# Forward.net
KiCad netlist of a schematic drawn in Altium Designer
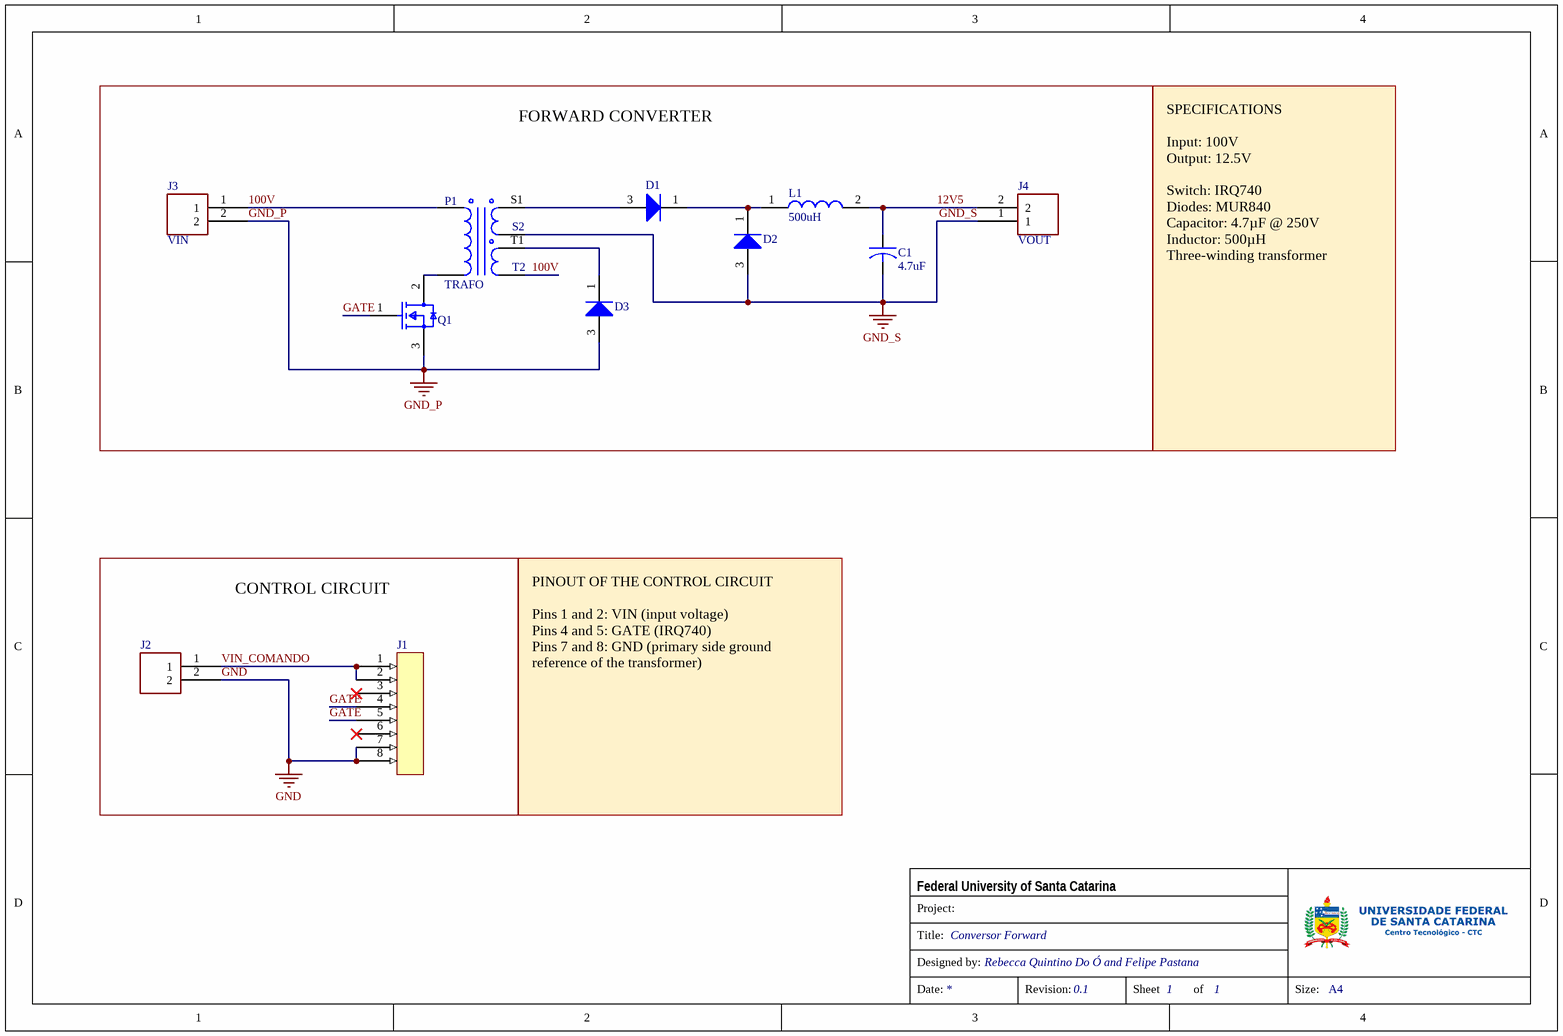
[diagram p0: Forward.SchDoc]

(export (version "E")
  (design (tool "Eeschema 10.0.6"))
  (components
    (comp (ref "C1")
      (value "4.7uF")
      (footprint "Capacitor")
      (description "Electrolytic capacitor")
      (libsource (lib "Elet_pot_2") (part "Capacitor Eletro"))
    )
    (comp (ref "D1")
      (value "MUR840G")
      (footprint "MUR840")
      (description "DIODE STANDARD 400V 8A TO2202")
      (libsource (lib "Elet_pot_2") (part "mur840"))
    )
    (comp (ref "D2")
      (value "MUR840G")
      (footprint "MUR840")
      (description "DIODE STANDARD 400V 8A TO2202")
      (libsource (lib "Elet_pot_2") (part "mur840"))
    )
    (comp (ref "D3")
      (value "MUR840G")
      (footprint "MUR840")
      (description "DIODE STANDARD 400V 8A TO2202")
      (libsource (lib "Elet_pot_2") (part "mur840"))
    )
    (comp (ref "J1")
      (value "header 8pin")
      (footprint "Header 8pin")
      (description "Header 8pin")
      (libsource (lib "Elet_pot_2") (part "header 8pin"))
    )
    (comp (ref "J2")
      (value "Con_Molex_2_pin")
      (footprint "CON_MOLEX_2_vias")
      (description "Connector KK Male 180° 2 Pins")
      (libsource (lib "Elet_pot_2") (part "Con_Molex_2_pin"))
    )
    (comp (ref "J3")
      (value "VIN")
      (footprint "Borne_KRE_2pin")
      (description "Connector Borne KRE 2 Vias")
      (libsource (lib "Elet_pot_2") (part "Borne_KRE_2_vias"))
    )
    (comp (ref "J4")
      (value "VOUT")
      (footprint "Borne_KRE_2pin")
      (description "Connector Borne KRE 2 Vias")
      (libsource (lib "") (part "Borne_KRE_2_vias_1"))
    )
    (comp (ref "L1")
      (value "500uH")
      (footprint "Indutor")
      (description "Indutor manufacture handmade")
      (libsource (lib "Elet_pot_2") (part "Indutor"))
    )
    (comp (ref "Q1")
      (value "IRF740")
      (footprint "IRF430")
      (description "MOSFET N-CH 400V 10A TO220AB")
      (libsource (lib "Elet_pot_2") (part "IRF740"))
    )
    (comp (ref "TRAFO")
      (value "Three-winding transformer")
      (footprint "Trafo_NEE_30/14")
      (description "Handmade three-winding transformer")
      (libsource (lib "Elet_pot_2") (part "Trafo"))
    )
  )
  (nets
    (net (code "1") (name "/12V5") (class "Default")
      (node (ref "C1") (pin "1") (pinfunction "1_1") (pintype "passive"))
      (node (ref "J4") (pin "2") (pinfunction "2_2") (pintype "passive"))
      (node (ref "L1") (pin "2") (pinfunction "2_2") (pintype "passive"))
    )
    (net (code "2") (name "/100V") (class "Default")
      (node (ref "J3") (pin "1") (pinfunction "1_1") (pintype "passive"))
      (node (ref "TRAFO") (pin "P1") (pinfunction "P1_P1") (pintype "passive"))
      (node (ref "TRAFO") (pin "S2") (pinfunction "S2_S2") (pintype "passive"))
    )
    (net (code "3") (name "/GATE") (class "Default")
      (node (ref "J1") (pin "4") (pinfunction "4_4") (pintype "input"))
      (node (ref "J1") (pin "5") (pinfunction "5_5") (pintype "input"))
      (node (ref "Q1") (pin "1") (pinfunction "G_1") (pintype "passive"))
    )
    (net (code "4") (name "/VIN_COMANDO") (class "Default")
      (node (ref "J1") (pin "1") (pinfunction "1_1") (pintype "input"))
      (node (ref "J1") (pin "2") (pinfunction "1_2") (pintype "input"))
      (node (ref "J2") (pin "1") (pinfunction "1_1") (pintype "passive"))
    )
    (net (code "5") (name "GND") (class "Default")
      (node (ref "J1") (pin "7") (pinfunction "7_7") (pintype "input"))
      (node (ref "J1") (pin "8") (pinfunction "8_8") (pintype "input"))
      (node (ref "J2") (pin "2") (pinfunction "2_2") (pintype "passive"))
    )
    (net (code "6") (name "GND_P") (class "Default")
      (node (ref "D3") (pin "3") (pinfunction "A_3") (pintype "passive"))
      (node (ref "J3") (pin "2") (pinfunction "2_2") (pintype "passive"))
      (node (ref "Q1") (pin "3") (pinfunction "S_3") (pintype "passive"))
    )
    (net (code "7") (name "GND_S") (class "Default")
      (node (ref "C1") (pin "2") (pinfunction "2_2") (pintype "passive"))
      (node (ref "D2") (pin "3") (pinfunction "A_3") (pintype "passive"))
      (node (ref "J4") (pin "1") (pinfunction "1_1") (pintype "passive"))
      (node (ref "TRAFO") (pin "S2") (pinfunction "S2_S2") (pintype "passive"))
    )
    (net (code "8") (name "Net-(D1-A)") (class "Default")
      (node (ref "D1") (pin "3") (pinfunction "A_3") (pintype "passive"))
      (node (ref "TRAFO") (pin "S1") (pinfunction "S1_S1") (pintype "passive"))
    )
    (net (code "9") (name "Net-(D1-K)") (class "Default")
      (node (ref "D1") (pin "1") (pinfunction "K_1") (pintype "passive"))
      (node (ref "D2") (pin "1") (pinfunction "K_1") (pintype "passive"))
      (node (ref "L1") (pin "1") (pinfunction "1_1") (pintype "passive"))
    )
    (net (code "10") (name "Net-(D3-K)") (class "Default")
      (node (ref "D3") (pin "1") (pinfunction "K_1") (pintype "passive"))
      (node (ref "TRAFO") (pin "T1") (pinfunction "T1_T1") (pintype "passive"))
    )
    (net (code "11") (name "Net-(Q1-D)") (class "Default")
      (node (ref "Q1") (pin "2") (pinfunction "D_2") (pintype "passive"))
      (node (ref "TRAFO") (pin "P2") (pinfunction "gg_P2") (pintype "passive"))
    )
    (net (code "12") (name "unconnected-(J1-Pad3)") (class "Default")
      (node (ref "J1") (pin "3") (pinfunction "3_3") (pintype "input+no_connect"))
    )
    (net (code "13") (name "unconnected-(J1-Pad6)") (class "Default")
      (node (ref "J1") (pin "6") (pinfunction "6_6") (pintype "input+no_connect"))
    )
  )
)
